# H-Bridge_using_MOSFET.net
KiCad netlist of a schematic drawn in Altium Designer
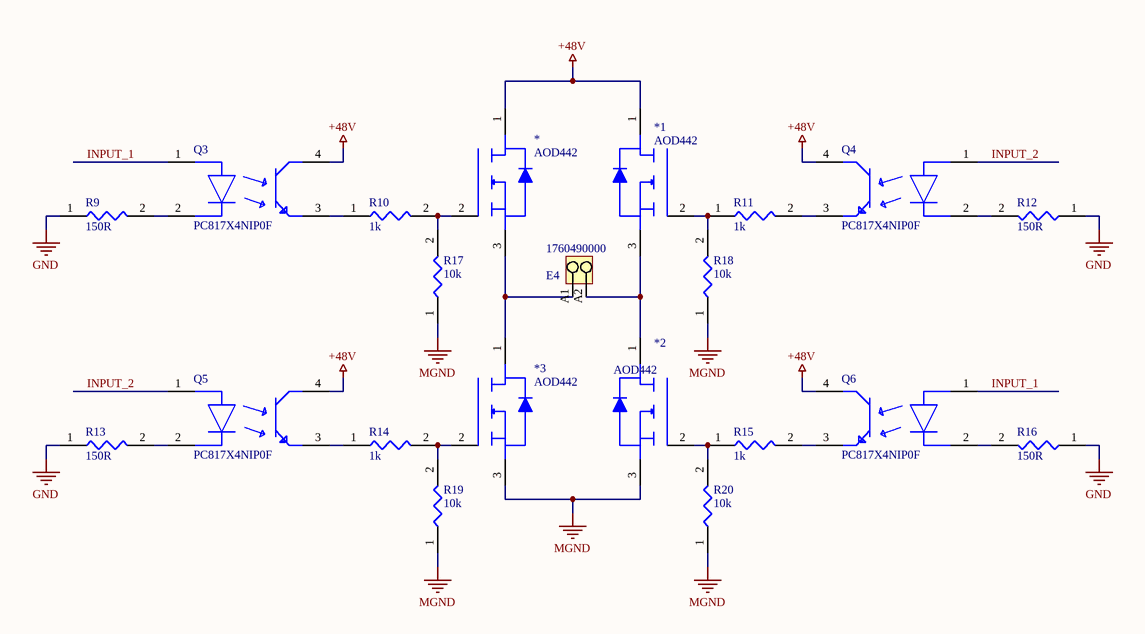
[diagram p0: H-Bridge using MOSFET.SchDoc]

(export (version "E")
  (design (tool "Eeschema 10.0.6"))
  (components
    (comp (ref "*") (value "AOD442") (libsource (lib "Power_MOSFET") (part "AOD442")))
    (comp (ref "*1") (value "AOD442") (libsource (lib "Power_MOSFET") (part "AOD442")))
    (comp (ref "*2") (value "AOD442") (libsource (lib "Power_MOSFET") (part "AOD442")))
    (comp (ref "*3") (value "AOD442") (libsource (lib "Power_MOSFET") (part "AOD442")))
    (comp (ref "E4")
      (value "1760490000")
      (footprint "PM_5_08_90_02")
      (description "OMNIMATE Signal - series PM")
      (fields (field (name "MANUFACTURER") "Weidmueller"))
      (libsource (lib "Altium Content Vault") (part "Terminal_02_1x02"))
    )
    (comp (ref "Q3")
      (value "PC817X4NIP0F")
      (footprint "FP-PC817X4NIP0F-MFG")
      (description "OPTOISOLATOR 5KV TRANS 4SMD")
      (fields
        (field (name "OCTOPART") "https://octopart.com/pc817x4nip0f-sharp-20650453")
        (field (name "MANUFACTURER") "Sharp")
      )
      (libsource (lib "Altium Content Vault") (part "8ff5844b63c0dea0057760e9ee25456"))
    )
    (comp (ref "Q4")
      (value "PC817X4NIP0F")
      (footprint "FP-PC817X4NIP0F-MFG")
      (description "OPTOISOLATOR 5KV TRANS 4SMD")
      (fields
        (field (name "OCTOPART") "https://octopart.com/pc817x4nip0f-sharp-20650453")
        (field (name "MANUFACTURER") "Sharp")
      )
      (libsource (lib "Altium Content Vault") (part "8ff5844b63c0dea0057760e9ee25456"))
    )
    (comp (ref "Q5")
      (value "PC817X4NIP0F")
      (footprint "FP-PC817X4NIP0F-MFG")
      (description "OPTOISOLATOR 5KV TRANS 4SMD")
      (fields
        (field (name "OCTOPART") "https://octopart.com/pc817x4nip0f-sharp-20650453")
        (field (name "MANUFACTURER") "Sharp")
      )
      (libsource (lib "Altium Content Vault") (part "8ff5844b63c0dea0057760e9ee25456"))
    )
    (comp (ref "Q6")
      (value "PC817X4NIP0F")
      (footprint "FP-PC817X4NIP0F-MFG")
      (description "OPTOISOLATOR 5KV TRANS 4SMD")
      (fields
        (field (name "OCTOPART") "https://octopart.com/pc817x4nip0f-sharp-20650453")
        (field (name "MANUFACTURER") "Sharp")
      )
      (libsource (lib "Altium Content Vault") (part "8ff5844b63c0dea0057760e9ee25456"))
    )
    (comp (ref "R9")
      (value "150R")
      (footprint "R0603 1k")
      (description "0603 1k Ohm 1% 1/10W")
      (fields
        (field (name "MANUFACTURER") "TE Connectivity")
        (field (name "MANUFACTURER PART NUMBER") "CRGCQ0603F1K0")
      )
      (libsource (lib "SectionE_BreakOut") (part "CRGCQ0603F1K0"))
    )
    (comp (ref "R10")
      (value "1k")
      (footprint "R0603 1k")
      (description "0603 1k Ohm 1% 1/10W")
      (fields
        (field (name "MANUFACTURER") "TE Connectivity")
        (field (name "MANUFACTURER PART NUMBER") "CRGCQ0603F1K0")
      )
      (libsource (lib "SectionE_BreakOut") (part "CRGCQ0603F1K0"))
    )
    (comp (ref "R11")
      (value "1k")
      (footprint "R0603 1k")
      (description "0603 1k Ohm 1% 1/10W")
      (fields
        (field (name "MANUFACTURER") "TE Connectivity")
        (field (name "MANUFACTURER PART NUMBER") "CRGCQ0603F1K0")
      )
      (libsource (lib "SectionE_BreakOut") (part "CRGCQ0603F1K0"))
    )
    (comp (ref "R12")
      (value "150R")
      (footprint "R0603 1k")
      (description "0603 1k Ohm 1% 1/10W")
      (fields
        (field (name "MANUFACTURER") "TE Connectivity")
        (field (name "MANUFACTURER PART NUMBER") "CRGCQ0603F1K0")
      )
      (libsource (lib "SectionE_BreakOut") (part "CRGCQ0603F1K0"))
    )
    (comp (ref "R13")
      (value "150R")
      (footprint "R0603 1k")
      (description "0603 1k Ohm 1% 1/10W")
      (fields
        (field (name "MANUFACTURER") "TE Connectivity")
        (field (name "MANUFACTURER PART NUMBER") "CRGCQ0603F1K0")
      )
      (libsource (lib "SectionE_BreakOut") (part "CRGCQ0603F1K0"))
    )
    (comp (ref "R14")
      (value "1k")
      (footprint "R0603 1k")
      (description "0603 1k Ohm 1% 1/10W")
      (fields
        (field (name "MANUFACTURER") "TE Connectivity")
        (field (name "MANUFACTURER PART NUMBER") "CRGCQ0603F1K0")
      )
      (libsource (lib "SectionE_BreakOut") (part "CRGCQ0603F1K0"))
    )
    (comp (ref "R15")
      (value "1k")
      (footprint "R0603 1k")
      (description "0603 1k Ohm 1% 1/10W")
      (fields
        (field (name "MANUFACTURER") "TE Connectivity")
        (field (name "MANUFACTURER PART NUMBER") "CRGCQ0603F1K0")
      )
      (libsource (lib "SectionE_BreakOut") (part "CRGCQ0603F1K0"))
    )
    (comp (ref "R16")
      (value "150R")
      (footprint "R0603 1k")
      (description "0603 1k Ohm 1% 1/10W")
      (fields
        (field (name "MANUFACTURER") "TE Connectivity")
        (field (name "MANUFACTURER PART NUMBER") "CRGCQ0603F1K0")
      )
      (libsource (lib "SectionE_BreakOut") (part "CRGCQ0603F1K0"))
    )
    (comp (ref "R17")
      (value "10k")
      (footprint "R0603 1k")
      (description "0603 1k Ohm 1% 1/10W")
      (fields
        (field (name "MANUFACTURER") "TE Connectivity")
        (field (name "MANUFACTURER PART NUMBER") "CRGCQ0603F1K0")
      )
      (libsource (lib "SectionE_BreakOut") (part "CRGCQ0603F1K0"))
    )
    (comp (ref "R18")
      (value "10k")
      (footprint "R0603 1k")
      (description "0603 1k Ohm 1% 1/10W")
      (fields
        (field (name "MANUFACTURER") "TE Connectivity")
        (field (name "MANUFACTURER PART NUMBER") "CRGCQ0603F1K0")
      )
      (libsource (lib "SectionE_BreakOut") (part "CRGCQ0603F1K0"))
    )
    (comp (ref "R19")
      (value "10k")
      (footprint "R0603 1k")
      (description "0603 1k Ohm 1% 1/10W")
      (fields
        (field (name "MANUFACTURER") "TE Connectivity")
        (field (name "MANUFACTURER PART NUMBER") "CRGCQ0603F1K0")
      )
      (libsource (lib "SectionE_BreakOut") (part "CRGCQ0603F1K0"))
    )
    (comp (ref "R20")
      (value "10k")
      (footprint "R0603 1k")
      (description "0603 1k Ohm 1% 1/10W")
      (fields
        (field (name "MANUFACTURER") "TE Connectivity")
        (field (name "MANUFACTURER PART NUMBER") "CRGCQ0603F1K0")
      )
      (libsource (lib "SectionE_BreakOut") (part "CRGCQ0603F1K0"))
    )
  )
  (nets
    (net (code "1") (name "+48V") (class "Default")
      (node (ref "*") (pin "1") (pinfunction "1_1") (pintype "passive"))
      (node (ref "*1") (pin "1") (pinfunction "1_1") (pintype "passive"))
      (node (ref "Q3") (pin "4") (pinfunction "C_4") (pintype "passive"))
      (node (ref "Q4") (pin "4") (pinfunction "C_4") (pintype "passive"))
      (node (ref "Q5") (pin "4") (pinfunction "C_4") (pintype "passive"))
      (node (ref "Q6") (pin "4") (pinfunction "C_4") (pintype "passive"))
    )
    (net (code "2") (name "/INPUT_1") (class "Default")
      (node (ref "Q3") (pin "1") (pinfunction "A_1") (pintype "passive"))
      (node (ref "Q6") (pin "1") (pinfunction "A_1") (pintype "passive"))
    )
    (net (code "3") (name "/INPUT_2") (class "Default")
      (node (ref "Q4") (pin "1") (pinfunction "A_1") (pintype "passive"))
      (node (ref "Q5") (pin "1") (pinfunction "A_1") (pintype "passive"))
    )
    (net (code "4") (name "GND") (class "Default")
      (node (ref "R12") (pin "1") (pinfunction "1_1") (pintype "passive"))
      (node (ref "R13") (pin "1") (pinfunction "1_1") (pintype "passive"))
      (node (ref "R16") (pin "1") (pinfunction "1_1") (pintype "passive"))
      (node (ref "R9") (pin "1") (pinfunction "1_1") (pintype "passive"))
    )
    (net (code "5") (name "MGND") (class "Default")
      (node (ref "*2") (pin "3") (pinfunction "3_3") (pintype "passive"))
      (node (ref "*3") (pin "3") (pinfunction "3_3") (pintype "passive"))
      (node (ref "R17") (pin "1") (pinfunction "1_1") (pintype "passive"))
      (node (ref "R18") (pin "1") (pinfunction "1_1") (pintype "passive"))
      (node (ref "R19") (pin "1") (pinfunction "1_1") (pintype "passive"))
      (node (ref "R20") (pin "1") (pinfunction "1_1") (pintype "passive"))
    )
    (net (code "6") (name "Net-(*-Pad2)") (class "Default")
      (node (ref "*") (pin "2") (pinfunction "2_2") (pintype "passive"))
      (node (ref "R10") (pin "2") (pinfunction "2_2") (pintype "passive"))
      (node (ref "R17") (pin "2") (pinfunction "2_2") (pintype "passive"))
    )
    (net (code "7") (name "Net-(*-Pad3)") (class "Default")
      (node (ref "*") (pin "3") (pinfunction "3_3") (pintype "passive"))
      (node (ref "*3") (pin "1") (pinfunction "1_1") (pintype "passive"))
      (node (ref "E4") (pin "A1") (pinfunction "A1_A1") (pintype "passive"))
    )
    (net (code "8") (name "Net-(*1-Pad2)") (class "Default")
      (node (ref "*1") (pin "2") (pinfunction "2_2") (pintype "passive"))
      (node (ref "R11") (pin "1") (pinfunction "1_1") (pintype "passive"))
      (node (ref "R18") (pin "2") (pinfunction "2_2") (pintype "passive"))
    )
    (net (code "9") (name "Net-(*1-Pad3)") (class "Default")
      (node (ref "*1") (pin "3") (pinfunction "3_3") (pintype "passive"))
      (node (ref "*2") (pin "1") (pinfunction "1_1") (pintype "passive"))
      (node (ref "E4") (pin "A2") (pinfunction "A2_A2") (pintype "passive"))
    )
    (net (code "10") (name "Net-(*2-Pad2)") (class "Default")
      (node (ref "*2") (pin "2") (pinfunction "2_2") (pintype "passive"))
      (node (ref "R15") (pin "1") (pinfunction "1_1") (pintype "passive"))
      (node (ref "R20") (pin "2") (pinfunction "2_2") (pintype "passive"))
    )
    (net (code "11") (name "Net-(*3-Pad2)") (class "Default")
      (node (ref "*3") (pin "2") (pinfunction "2_2") (pintype "passive"))
      (node (ref "R14") (pin "2") (pinfunction "2_2") (pintype "passive"))
      (node (ref "R19") (pin "2") (pinfunction "2_2") (pintype "passive"))
    )
    (net (code "12") (name "Net-(Q3-C-Pad2)") (class "Default")
      (node (ref "Q3") (pin "2") (pinfunction "C_2") (pintype "passive"))
      (node (ref "R9") (pin "2") (pinfunction "2_2") (pintype "passive"))
    )
    (net (code "13") (name "Net-(Q3-E)") (class "Default")
      (node (ref "Q3") (pin "3") (pinfunction "E_3") (pintype "passive"))
      (node (ref "R10") (pin "1") (pinfunction "1_1") (pintype "passive"))
    )
    (net (code "14") (name "Net-(Q4-C-Pad2)") (class "Default")
      (node (ref "Q4") (pin "2") (pinfunction "C_2") (pintype "passive"))
      (node (ref "R12") (pin "2") (pinfunction "2_2") (pintype "passive"))
    )
    (net (code "15") (name "Net-(Q4-E)") (class "Default")
      (node (ref "Q4") (pin "3") (pinfunction "E_3") (pintype "passive"))
      (node (ref "R11") (pin "2") (pinfunction "2_2") (pintype "passive"))
    )
    (net (code "16") (name "Net-(Q5-C-Pad2)") (class "Default")
      (node (ref "Q5") (pin "2") (pinfunction "C_2") (pintype "passive"))
      (node (ref "R13") (pin "2") (pinfunction "2_2") (pintype "passive"))
    )
    (net (code "17") (name "Net-(Q5-E)") (class "Default")
      (node (ref "Q5") (pin "3") (pinfunction "E_3") (pintype "passive"))
      (node (ref "R14") (pin "1") (pinfunction "1_1") (pintype "passive"))
    )
    (net (code "18") (name "Net-(Q6-C-Pad2)") (class "Default")
      (node (ref "Q6") (pin "2") (pinfunction "C_2") (pintype "passive"))
      (node (ref "R16") (pin "2") (pinfunction "2_2") (pintype "passive"))
    )
    (net (code "19") (name "Net-(Q6-E)") (class "Default")
      (node (ref "Q6") (pin "3") (pinfunction "E_3") (pintype "passive"))
      (node (ref "R15") (pin "2") (pinfunction "2_2") (pintype "passive"))
    )
  )
)
